# jalapino.net
KiCad netlist of a schematic drawn in EAGLE
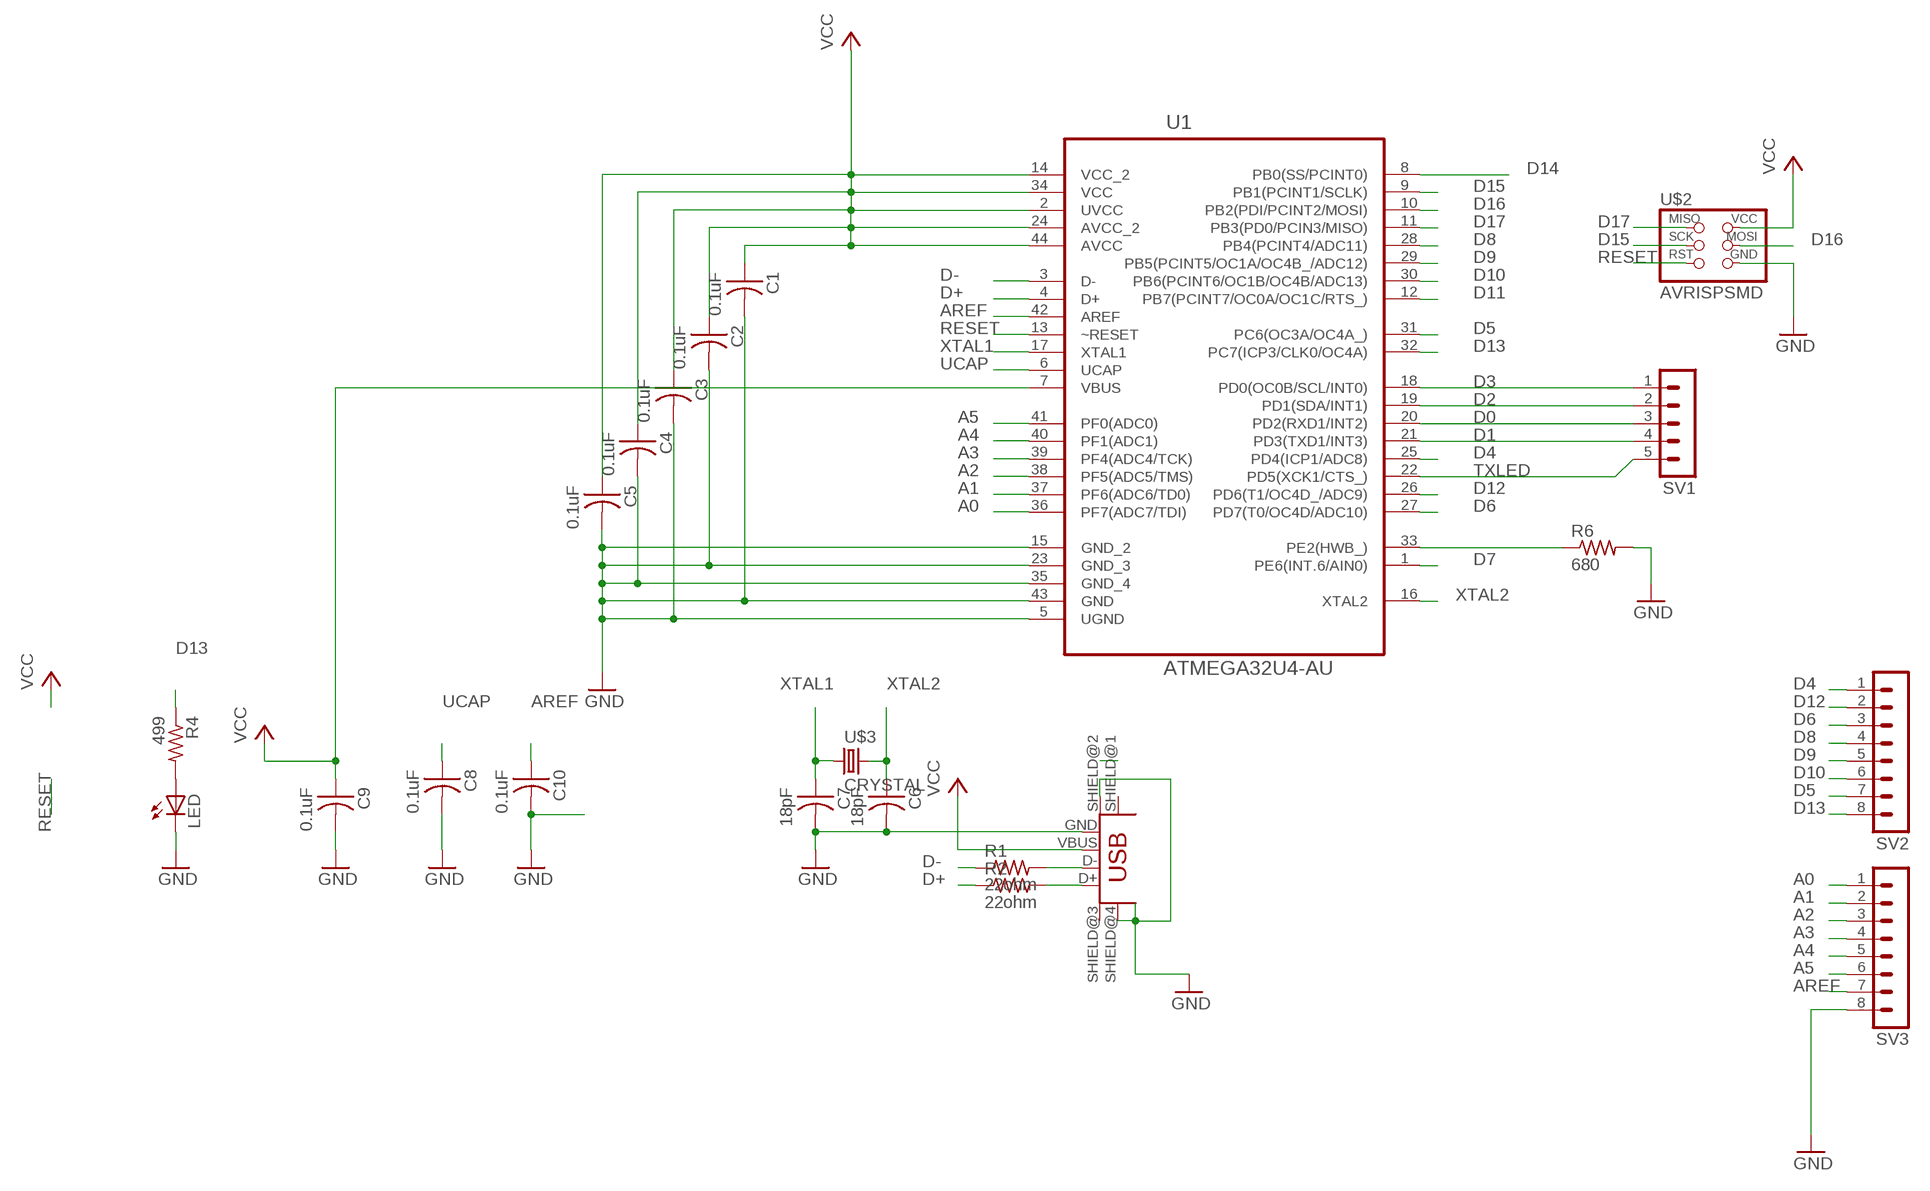
[diagram p0: schematic, sheet 1]

(export (version "E")
  (design (tool "Eeschema 10.0.6"))
  (components
    (comp (ref "C1")
      (value "0.1uF")
      (footprint "eagle-import:C1206FAB")
      (libsource (lib "eagle-import") (part "CAP-US1206FAB"))
    )
    (comp (ref "C2")
      (value "0.1uF")
      (footprint "eagle-import:C1206FAB")
      (libsource (lib "eagle-import") (part "CAP-US1206FAB"))
    )
    (comp (ref "C3")
      (value "0.1uF")
      (footprint "eagle-import:C1206FAB")
      (libsource (lib "eagle-import") (part "CAP-US1206FAB"))
    )
    (comp (ref "C4")
      (value "0.1uF")
      (footprint "eagle-import:C1206FAB")
      (libsource (lib "eagle-import") (part "CAP-US1206FAB"))
    )
    (comp (ref "C5")
      (value "0.1uF")
      (footprint "eagle-import:C1206FAB")
      (libsource (lib "eagle-import") (part "CAP-US1206FAB"))
    )
    (comp (ref "C6")
      (value "18pF")
      (footprint "eagle-import:C1206FAB")
      (libsource (lib "eagle-import") (part "CAP-US1206FAB"))
    )
    (comp (ref "C7")
      (value "18pF")
      (footprint "eagle-import:C1206FAB")
      (libsource (lib "eagle-import") (part "CAP-US1206FAB"))
    )
    (comp (ref "C8")
      (value "0.1uF")
      (footprint "eagle-import:C1206FAB")
      (libsource (lib "eagle-import") (part "CAP-US1206FAB"))
    )
    (comp (ref "C9")
      (value "0.1uF")
      (footprint "eagle-import:C1206FAB")
      (libsource (lib "eagle-import") (part "CAP-US1206FAB"))
    )
    (comp (ref "C10")
      (value "0.1uF")
      (footprint "eagle-import:C1206FAB")
      (libsource (lib "eagle-import") (part "CAP-US1206FAB"))
    )
    (comp (ref "LED")
      (value "LED1206")
      (footprint "eagle-import:1206")
      (libsource (lib "eagle-import") (part "LED1206"))
    )
    (comp (ref "R1")
      (value "22ohm")
      (footprint "eagle-import:R1206FAB")
      (libsource (lib "eagle-import") (part "RES-US1206FAB"))
    )
    (comp (ref "R2")
      (value "22ohm")
      (footprint "eagle-import:R1206FAB")
      (libsource (lib "eagle-import") (part "RES-US1206FAB"))
    )
    (comp (ref "R4")
      (value "499")
      (footprint "eagle-import:1206")
      (libsource (lib "eagle-import") (part "RESISTOR1206"))
    )
    (comp (ref "R6")
      (value "680")
      (footprint "eagle-import:R1206FAB")
      (libsource (lib "eagle-import") (part "RES-US1206FAB"))
    )
    (comp (ref "SV1")
      (value "MA05-1")
      (footprint "eagle-import:MA05-1")
      (libsource (lib "eagle-import") (part "MA05-1"))
    )
    (comp (ref "SV2")
      (value "MA08-1")
      (footprint "eagle-import:MA08-1")
      (libsource (lib "eagle-import") (part "MA08-1"))
    )
    (comp (ref "SV3")
      (value "MA08-1")
      (footprint "eagle-import:MA08-1")
      (libsource (lib "eagle-import") (part "MA08-1"))
    )
    (comp (ref "U$1")
      (value "USB_MINIB")
      (footprint "eagle-import:USB_MINIB")
      (libsource (lib "eagle-import") (part "USB_MINIB"))
    )
    (comp (ref "U$2")
      (value "AVRISPSMD")
      (footprint "eagle-import:2X03SMD")
      (libsource (lib "eagle-import") (part "AVRISPSMD"))
    )
    (comp (ref "U$3")
      (value "CRYSTAL")
      (footprint "eagle-import:2-SMD-5X3MM")
      (libsource (lib "eagle-import") (part "CRYSTAL"))
    )
    (comp (ref "U1")
      (value "ATMEGA32U4-AU")
      (footprint "eagle-import:QFP80P1200X1200X120-44N")
      (libsource (lib "eagle-import") (part "ATMEGA32U4-AU"))
    )
  )
  (nets
    (net (code "1") (name "/A0") (class "Default")
      (node (ref "SV3") (pin "1") (pinfunction "1_1") (pintype "passive"))
      (node (ref "U1") (pin "36") (pinfunction "PF7(ADC7/TDI)_36") (pintype "bidirectional"))
    )
    (net (code "2") (name "/A1") (class "Default")
      (node (ref "SV3") (pin "2") (pinfunction "2_2") (pintype "passive"))
      (node (ref "U1") (pin "37") (pinfunction "PF6(ADC6/TD0)_37") (pintype "bidirectional"))
    )
    (net (code "3") (name "/A2") (class "Default")
      (node (ref "SV3") (pin "3") (pinfunction "3_3") (pintype "passive"))
      (node (ref "U1") (pin "38") (pinfunction "PF5(ADC5/TMS)_38") (pintype "bidirectional"))
    )
    (net (code "4") (name "/A3") (class "Default")
      (node (ref "SV3") (pin "4") (pinfunction "4_4") (pintype "passive"))
      (node (ref "U1") (pin "39") (pinfunction "PF4(ADC4/TCK)_39") (pintype "bidirectional"))
    )
    (net (code "5") (name "/A4") (class "Default")
      (node (ref "SV3") (pin "5") (pinfunction "5_5") (pintype "passive"))
      (node (ref "U1") (pin "40") (pinfunction "PF1(ADC1)_40") (pintype "bidirectional"))
    )
    (net (code "6") (name "/A5") (class "Default")
      (node (ref "SV3") (pin "6") (pinfunction "6_6") (pintype "passive"))
      (node (ref "U1") (pin "41") (pinfunction "PF0(ADC0)_41") (pintype "bidirectional"))
    )
    (net (code "7") (name "/AREF") (class "Default")
      (node (ref "C10") (pin "1") (pinfunction "1_1") (pintype "passive"))
      (node (ref "SV3") (pin "7") (pinfunction "7_7") (pintype "passive"))
      (node (ref "U1") (pin "42") (pinfunction "AREF_42") (pintype "input"))
    )
    (net (code "8") (name "/D+") (class "Default")
      (node (ref "R2") (pin "1") (pinfunction "1_1") (pintype "passive"))
      (node (ref "U1") (pin "4") (pinfunction "D+_4") (pintype "passive"))
    )
    (net (code "9") (name "/D-") (class "Default")
      (node (ref "R1") (pin "1") (pinfunction "1_1") (pintype "passive"))
      (node (ref "U1") (pin "3") (pinfunction "D-_3") (pintype "passive"))
    )
    (net (code "10") (name "/D0") (class "Default")
      (node (ref "SV1") (pin "3") (pinfunction "3_3") (pintype "passive"))
      (node (ref "U1") (pin "20") (pinfunction "PD2(RXD1/INT2)_20") (pintype "bidirectional"))
    )
    (net (code "11") (name "/D1") (class "Default")
      (node (ref "SV1") (pin "4") (pinfunction "4_4") (pintype "passive"))
      (node (ref "U1") (pin "21") (pinfunction "PD3(TXD1/INT3)_21") (pintype "bidirectional"))
    )
    (net (code "12") (name "/D2") (class "Default")
      (node (ref "SV1") (pin "2") (pinfunction "2_2") (pintype "passive"))
      (node (ref "U1") (pin "19") (pinfunction "PD1(SDA/INT1)_19") (pintype "bidirectional"))
    )
    (net (code "13") (name "/D3") (class "Default")
      (node (ref "SV1") (pin "1") (pinfunction "1_1") (pintype "passive"))
      (node (ref "U1") (pin "18") (pinfunction "PD0(OC0B/SCL/INT0)_18") (pintype "bidirectional"))
    )
    (net (code "14") (name "/D4") (class "Default")
      (node (ref "SV2") (pin "1") (pinfunction "1_1") (pintype "passive"))
      (node (ref "U1") (pin "25") (pinfunction "PD4(ICP1/ADC8)_25") (pintype "bidirectional"))
    )
    (net (code "15") (name "/D5") (class "Default")
      (node (ref "SV2") (pin "7") (pinfunction "7_7") (pintype "passive"))
      (node (ref "U1") (pin "31") (pinfunction "PC6(OC3A/OC4A_)_31") (pintype "bidirectional"))
    )
    (net (code "16") (name "/D6") (class "Default")
      (node (ref "SV2") (pin "3") (pinfunction "3_3") (pintype "passive"))
      (node (ref "U1") (pin "27") (pinfunction "PD7(T0/OC4D/ADC10)_27") (pintype "bidirectional"))
    )
    (net (code "17") (name "/D7") (class "Default")
      (node (ref "U1") (pin "1") (pinfunction "PE6(INT.6/AIN0)_1") (pintype "bidirectional"))
    )
    (net (code "18") (name "/D8") (class "Default")
      (node (ref "SV2") (pin "4") (pinfunction "4_4") (pintype "passive"))
      (node (ref "U1") (pin "28") (pinfunction "PB4(PCINT4/ADC11)_28") (pintype "bidirectional"))
    )
    (net (code "19") (name "/D9") (class "Default")
      (node (ref "SV2") (pin "5") (pinfunction "5_5") (pintype "passive"))
      (node (ref "U1") (pin "29") (pinfunction "PB5(PCINT5/OC1A/OC4B_/ADC12)_29") (pintype "bidirectional"))
    )
    (net (code "20") (name "/D10") (class "Default")
      (node (ref "SV2") (pin "6") (pinfunction "6_6") (pintype "passive"))
      (node (ref "U1") (pin "30") (pinfunction "PB6(PCINT6/OC1B/OC4B/ADC13)_30") (pintype "bidirectional"))
    )
    (net (code "21") (name "/D11") (class "Default")
      (node (ref "U1") (pin "12") (pinfunction "PB7(PCINT7/OC0A/OC1C/RTS_)_12") (pintype "bidirectional"))
    )
    (net (code "22") (name "/D12") (class "Default")
      (node (ref "SV2") (pin "2") (pinfunction "2_2") (pintype "passive"))
      (node (ref "U1") (pin "26") (pinfunction "PD6(T1/OC4D_/ADC9)_26") (pintype "bidirectional"))
    )
    (net (code "23") (name "/D13") (class "Default")
      (node (ref "R4") (pin "1") (pinfunction "1_1") (pintype "passive"))
      (node (ref "SV2") (pin "8") (pinfunction "8_8") (pintype "passive"))
      (node (ref "U1") (pin "32") (pinfunction "PC7(ICP3/CLK0/OC4A)_32") (pintype "bidirectional"))
    )
    (net (code "24") (name "/D14") (class "Default")
      (node (ref "U1") (pin "8") (pinfunction "PB0(SS/PCINT0)_8") (pintype "bidirectional"))
    )
    (net (code "25") (name "/D15") (class "Default")
      (node (ref "U$2") (pin "3") (pinfunction "SCK_3") (pintype "passive"))
      (node (ref "U1") (pin "9") (pinfunction "PB1(PCINT1/SCLK)_9") (pintype "bidirectional"))
    )
    (net (code "26") (name "/D16") (class "Default")
      (node (ref "U$2") (pin "4") (pinfunction "MOSI_4") (pintype "passive"))
      (node (ref "U1") (pin "10") (pinfunction "PB2(PDI/PCINT2/MOSI)_10") (pintype "bidirectional"))
    )
    (net (code "27") (name "/D17") (class "Default")
      (node (ref "U$2") (pin "1") (pinfunction "MISO_1") (pintype "passive"))
      (node (ref "U1") (pin "11") (pinfunction "PB3(PD0/PCIN3/MISO)_11") (pintype "bidirectional"))
    )
    (net (code "28") (name "/RESET") (class "Default")
      (node (ref "U$2") (pin "5") (pinfunction "RST_5") (pintype "passive"))
      (node (ref "U1") (pin "13") (pinfunction "~{RESET}_13") (pintype "input"))
    )
    (net (code "29") (name "/TXLED") (class "Default")
      (node (ref "SV1") (pin "5") (pinfunction "5_5") (pintype "passive"))
      (node (ref "U1") (pin "22") (pinfunction "PD5(XCK1/CTS_)_22") (pintype "bidirectional"))
    )
    (net (code "30") (name "/UCAP") (class "Default")
      (node (ref "C8") (pin "1") (pinfunction "1_1") (pintype "passive"))
      (node (ref "U1") (pin "6") (pinfunction "UCAP_6") (pintype "power_in"))
    )
    (net (code "31") (name "/XTAL1") (class "Default")
      (node (ref "C7") (pin "1") (pinfunction "1_1") (pintype "passive"))
      (node (ref "U$3") (pin "P$1") (pinfunction "1_P$1") (pintype "passive"))
      (node (ref "U1") (pin "17") (pinfunction "XTAL1_17") (pintype "input"))
    )
    (net (code "32") (name "/XTAL2") (class "Default")
      (node (ref "C6") (pin "1") (pinfunction "1_1") (pintype "passive"))
      (node (ref "U$3") (pin "P$2") (pinfunction "2_P$2") (pintype "passive"))
      (node (ref "U1") (pin "16") (pinfunction "XTAL2_16") (pintype "output"))
    )
    (net (code "33") (name "GND") (class "Default")
      (node (ref "C1") (pin "2") (pinfunction "2_2") (pintype "passive"))
      (node (ref "C10") (pin "2") (pinfunction "2_2") (pintype "passive"))
      (node (ref "C2") (pin "2") (pinfunction "2_2") (pintype "passive"))
      (node (ref "C3") (pin "2") (pinfunction "2_2") (pintype "passive"))
      (node (ref "C4") (pin "2") (pinfunction "2_2") (pintype "passive"))
      (node (ref "C5") (pin "2") (pinfunction "2_2") (pintype "passive"))
      (node (ref "C6") (pin "2") (pinfunction "2_2") (pintype "passive"))
      (node (ref "C7") (pin "2") (pinfunction "2_2") (pintype "passive"))
      (node (ref "C8") (pin "2") (pinfunction "2_2") (pintype "passive"))
      (node (ref "C9") (pin "2") (pinfunction "2_2") (pintype "passive"))
      (node (ref "LED") (pin "2") (pinfunction "C_2") (pintype "passive"))
      (node (ref "R6") (pin "2") (pinfunction "2_2") (pintype "passive"))
      (node (ref "SV3") (pin "8") (pinfunction "8_8") (pintype "passive"))
      (node (ref "U$1") (pin "GND") (pinfunction "GND_GND") (pintype "bidirectional"))
      (node (ref "U$1") (pin "SHIELD@2") (pinfunction "SHIELD1_SHIELD@2") (pintype "passive"))
      (node (ref "U$1") (pin "SHIELD@4") (pinfunction "SHIELD3_SHIELD@4") (pintype "passive"))
      (node (ref "U$2") (pin "6") (pinfunction "GND_6") (pintype "passive"))
      (node (ref "U1") (pin "15") (pinfunction "GND_2_15") (pintype "passive"))
      (node (ref "U1") (pin "23") (pinfunction "GND_3_23") (pintype "passive"))
      (node (ref "U1") (pin "35") (pinfunction "GND_4_35") (pintype "passive"))
      (node (ref "U1") (pin "43") (pinfunction "GND_43") (pintype "passive"))
      (node (ref "U1") (pin "5") (pinfunction "UGND_5") (pintype "passive"))
    )
    (net (code "34") (name "Net-(LED-A)") (class "Default")
      (node (ref "LED") (pin "1") (pinfunction "A_1") (pintype "passive"))
      (node (ref "R4") (pin "2") (pinfunction "2_2") (pintype "passive"))
    )
    (net (code "35") (name "Net-(R1-Pad2)") (class "Default")
      (node (ref "R1") (pin "2") (pinfunction "2_2") (pintype "passive"))
      (node (ref "U$1") (pin "D-") (pinfunction "D-_D-") (pintype "bidirectional"))
    )
    (net (code "36") (name "Net-(R2-Pad2)") (class "Default")
      (node (ref "R2") (pin "2") (pinfunction "2_2") (pintype "passive"))
      (node (ref "U$1") (pin "D+") (pinfunction "D+_D+") (pintype "bidirectional"))
    )
    (net (code "37") (name "Net-(U1-PE2(HWB_))") (class "Default")
      (node (ref "R6") (pin "1") (pinfunction "1_1") (pintype "passive"))
      (node (ref "U1") (pin "33") (pinfunction "PE2(HWB_)_33") (pintype "bidirectional"))
    )
    (net (code "38") (name "VCC") (class "Default")
      (node (ref "C1") (pin "1") (pinfunction "1_1") (pintype "passive"))
      (node (ref "C2") (pin "1") (pinfunction "1_1") (pintype "passive"))
      (node (ref "C3") (pin "1") (pinfunction "1_1") (pintype "passive"))
      (node (ref "C4") (pin "1") (pinfunction "1_1") (pintype "passive"))
      (node (ref "C5") (pin "1") (pinfunction "1_1") (pintype "passive"))
      (node (ref "C9") (pin "1") (pinfunction "1_1") (pintype "passive"))
      (node (ref "U$1") (pin "VBUS") (pinfunction "VBUS_VBUS") (pintype "bidirectional"))
      (node (ref "U$2") (pin "2") (pinfunction "VCC_2") (pintype "passive"))
      (node (ref "U1") (pin "14") (pinfunction "VCC_2_14") (pintype "power_in"))
      (node (ref "U1") (pin "2") (pinfunction "UVCC_2") (pintype "power_in"))
      (node (ref "U1") (pin "24") (pinfunction "AVCC_2_24") (pintype "power_in"))
      (node (ref "U1") (pin "34") (pinfunction "VCC_34") (pintype "power_in"))
      (node (ref "U1") (pin "44") (pinfunction "AVCC_44") (pintype "power_in"))
      (node (ref "U1") (pin "7") (pinfunction "VBUS_7") (pintype "input"))
    )
    (net (code "39") (name "unconnected-(U$1-SHIELD-PadSHIELD@1)") (class "Default")
      (node (ref "U$1") (pin "SHIELD@1") (pinfunction "SHIELD_SHIELD@1") (pintype "passive"))
    )
    (net (code "40") (name "unconnected-(U$1-SHIELD2-PadSHIELD@3)") (class "Default")
      (node (ref "U$1") (pin "SHIELD@3") (pinfunction "SHIELD2_SHIELD@3") (pintype "passive"))
    )
  )
)
